# AutomaTiles_LiPo_Charger.net
KiCad netlist of a schematic drawn in EAGLE
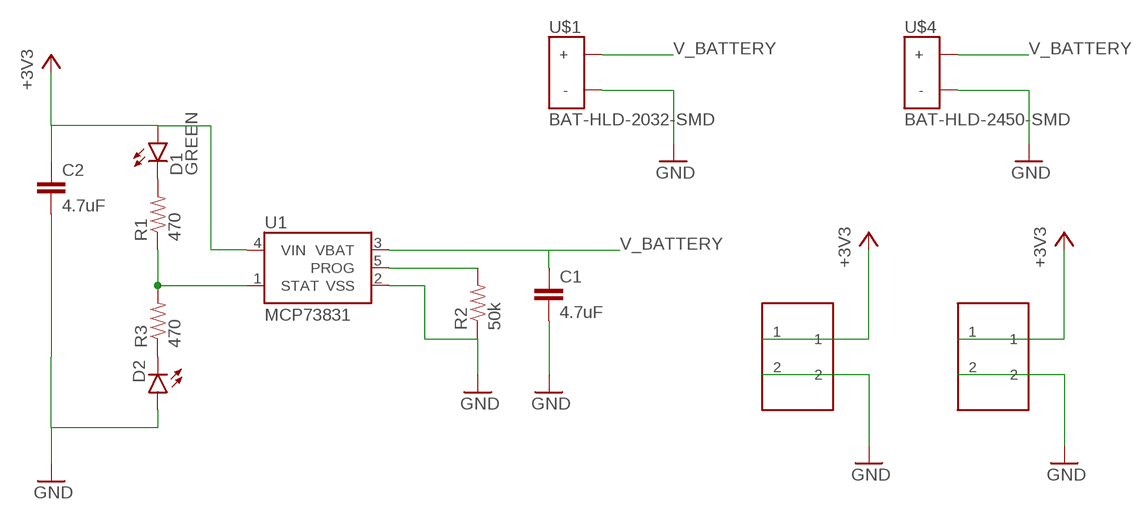
[diagram p0: schematic, sheet 1]

(export (version "E")
  (design (tool "Eeschema 10.0.6"))
  (components
    (comp (ref "C1")
      (value "4.7uF")
      (footprint "eagle-import:0603-CAP")
      (libsource (lib "eagle-import") (part "4.7UF-6.3V-10%(0603)0603"))
    )
    (comp (ref "C2")
      (value "4.7uF")
      (footprint "eagle-import:0603-CAP")
      (libsource (lib "eagle-import") (part "4.7UF-6.3V-10%(0603)0603"))
    )
    (comp (ref "D1")
      (value "GREEN")
      (footprint "eagle-import:LED-0603")
      (libsource (lib "eagle-import") (part "LED-GREEN0603"))
    )
    (comp (ref "D2")
      (value "LED-YELLOW0603")
      (footprint "eagle-import:LED-0603")
      (libsource (lib "eagle-import") (part "LED-YELLOW0603"))
    )
    (comp (ref "R1")
      (value "470")
      (footprint "eagle-import:0603-RES")
      (libsource (lib "eagle-import") (part "470OHM1/10W1%(0603)"))
    )
    (comp (ref "R2")
      (value "50k")
      (footprint "eagle-import:0603-RES")
      (libsource (lib "eagle-import") (part "2.0KOHM1/10W5%(0603)"))
    )
    (comp (ref "R3")
      (value "470")
      (footprint "eagle-import:0603-RES")
      (libsource (lib "eagle-import") (part "470OHM1/10W1%(0603)"))
    )
    (comp (ref "U$1")
      (value "BAT-HLD-2032-SMD")
      (footprint "eagle-import:BAT-HLD-2032-SMD")
      (libsource (lib "eagle-import") (part "BAT-HLD-2032-SMD"))
    )
    (comp (ref "U$2")
      (value "1X2_FEMALE_HEADER")
      (footprint "eagle-import:1X2_FEMALE_HEADER")
      (libsource (lib "eagle-import") (part "1X2_FEMALE_HEADER"))
    )
    (comp (ref "U$3")
      (value "1X2_FEMALE_HEADER")
      (footprint "eagle-import:1X2_FEMALE_HEADER")
      (libsource (lib "eagle-import") (part "1X2_FEMALE_HEADER"))
    )
    (comp (ref "U$4")
      (value "BAT-HLD-2450-SMD")
      (footprint "eagle-import:BAT-HLD-2450-SMD")
      (libsource (lib "eagle-import") (part "BAT-HLD-2450-SMD"))
    )
    (comp (ref "U1")
      (value "MCP73831")
      (footprint "eagle-import:SOT23-5")
      (libsource (lib "eagle-import") (part "MCP73831"))
    )
  )
  (nets
    (net (code "1") (name "+3V3") (class "Default")
      (node (ref "C2") (pin "1") (pinfunction "1_1") (pintype "passive"))
      (node (ref "D1") (pin "A") (pinfunction "A_A") (pintype "passive"))
      (node (ref "U$2") (pin "1") (pinfunction "1_1") (pintype "bidirectional"))
      (node (ref "U$3") (pin "1") (pinfunction "1_1") (pintype "bidirectional"))
      (node (ref "U1") (pin "4") (pinfunction "VIN_4") (pintype "power_in"))
    )
    (net (code "2") (name "/V_BATTERY") (class "Default")
      (node (ref "C1") (pin "1") (pinfunction "1_1") (pintype "passive"))
      (node (ref "U$1") (pin "POS1") (pinfunction "+_POS1") (pintype "bidirectional"))
      (node (ref "U$1") (pin "POS2") (pinfunction "+_POS2") (pintype "bidirectional"))
      (node (ref "U$4") (pin "POS1") (pinfunction "+_POS1") (pintype "bidirectional"))
      (node (ref "U$4") (pin "POS2") (pinfunction "+_POS2") (pintype "bidirectional"))
      (node (ref "U1") (pin "3") (pinfunction "VBAT_3") (pintype "power_in"))
    )
    (net (code "3") (name "GND") (class "Default")
      (node (ref "C1") (pin "2") (pinfunction "2_2") (pintype "passive"))
      (node (ref "C2") (pin "2") (pinfunction "2_2") (pintype "passive"))
      (node (ref "D2") (pin "A") (pinfunction "A_A") (pintype "passive"))
      (node (ref "R2") (pin "1") (pinfunction "1_1") (pintype "passive"))
      (node (ref "U$1") (pin "GND") (pinfunction "-_GND") (pintype "bidirectional"))
      (node (ref "U$2") (pin "2") (pinfunction "2_2") (pintype "bidirectional"))
      (node (ref "U$3") (pin "2") (pinfunction "2_2") (pintype "bidirectional"))
      (node (ref "U$4") (pin "GND") (pinfunction "-_GND") (pintype "bidirectional"))
      (node (ref "U1") (pin "2") (pinfunction "VSS_2") (pintype "power_in"))
    )
    (net (code "4") (name "Net-(D1-PadC)") (class "Default")
      (node (ref "D1") (pin "C") (pinfunction "C_C") (pintype "passive"))
      (node (ref "R1") (pin "2") (pinfunction "2_2") (pintype "passive"))
    )
    (net (code "5") (name "Net-(D2-PadC)") (class "Default")
      (node (ref "D2") (pin "C") (pinfunction "C_C") (pintype "passive"))
      (node (ref "R3") (pin "1") (pinfunction "1_1") (pintype "passive"))
    )
    (net (code "6") (name "Net-(U1-PROG)") (class "Default")
      (node (ref "R2") (pin "2") (pinfunction "2_2") (pintype "passive"))
      (node (ref "U1") (pin "5") (pinfunction "PROG_5") (pintype "input"))
    )
    (net (code "7") (name "Net-(U1-STAT)") (class "Default")
      (node (ref "R1") (pin "1") (pinfunction "1_1") (pintype "passive"))
      (node (ref "R3") (pin "2") (pinfunction "2_2") (pintype "passive"))
      (node (ref "U1") (pin "1") (pinfunction "STAT_1") (pintype "output"))
    )
  )
)
